# pub.net
KiCad netlist of a schematic drawn in EAGLE
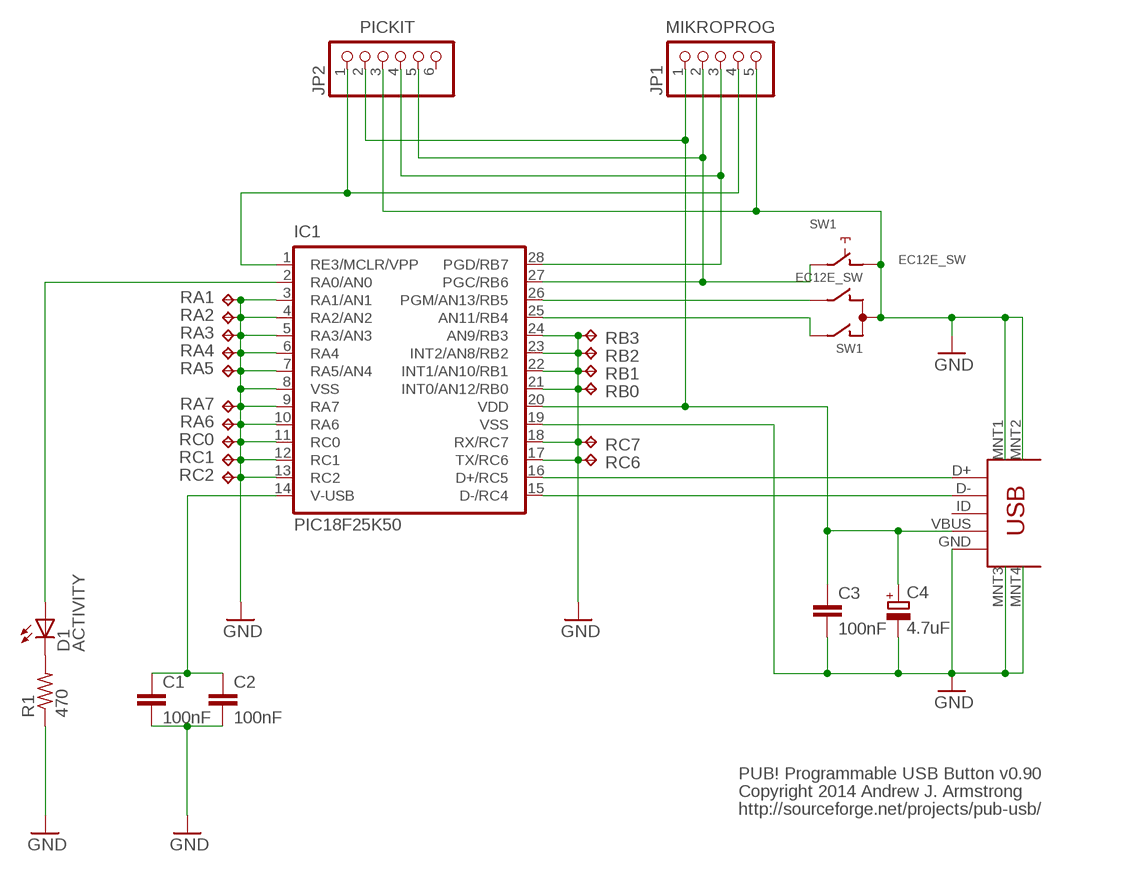
[diagram p0: schematic, sheet 1]

(export (version "E")
  (design (tool "Eeschema 10.0.6"))
  (components
    (comp (ref "C1")
      (value "100nF")
      (footprint "eagle-import:C0805")
      (libsource (lib "eagle-import") (part "C-EUC0805"))
    )
    (comp (ref "C2")
      (value "100nF")
      (footprint "eagle-import:C0805")
      (libsource (lib "eagle-import") (part "C-EUC0805"))
    )
    (comp (ref "C3")
      (value "100nF")
      (footprint "eagle-import:C0805")
      (libsource (lib "eagle-import") (part "C-EUC0805"))
    )
    (comp (ref "C4")
      (value "4.7uF")
      (footprint "eagle-import:SMC_A")
      (libsource (lib "eagle-import") (part "CPOL-EUSMCA"))
    )
    (comp (ref "D1")
      (value "ACTIVITY")
      (footprint "eagle-import:SML1206")
      (libsource (lib "eagle-import") (part "LEDSML1206"))
    )
    (comp (ref "IC1")
      (value "PIC18F25K50")
      (footprint "eagle-import:SO28W")
      (libsource (lib "eagle-import") (part "PIC18F25K50SO28W"))
    )
    (comp (ref "JP1")
      (value "MIKROPROG")
      (footprint "eagle-import:1X05_90")
      (libsource (lib "eagle-import") (part "PINHD-1X5/90"))
    )
    (comp (ref "JP2")
      (value "PICKIT")
      (footprint "eagle-import:1X06_90")
      (libsource (lib "eagle-import") (part "PINHD-1X6/90"))
    )
    (comp (ref "JP3")
      (value "USB-MINIB-5PIN")
      (footprint "eagle-import:USB-MINIB")
      (libsource (lib "eagle-import") (part "USB-MINIB-5PIN"))
    )
    (comp (ref "R1")
      (value "470")
      (footprint "eagle-import:M1206")
      (libsource (lib "eagle-import") (part "R-US_M1206"))
    )
    (comp (ref "RA1")
      (value "TPB1,27")
      (footprint "eagle-import:B1,27")
      (libsource (lib "eagle-import") (part "TPB1,27"))
    )
    (comp (ref "RA2")
      (value "TPB1,27")
      (footprint "eagle-import:B1,27")
      (libsource (lib "eagle-import") (part "TPB1,27"))
    )
    (comp (ref "RA3")
      (value "TPB1,27")
      (footprint "eagle-import:B1,27")
      (libsource (lib "eagle-import") (part "TPB1,27"))
    )
    (comp (ref "RA4")
      (value "TPB1,27")
      (footprint "eagle-import:B1,27")
      (libsource (lib "eagle-import") (part "TPB1,27"))
    )
    (comp (ref "RA5")
      (value "TPB1,27")
      (footprint "eagle-import:B1,27")
      (libsource (lib "eagle-import") (part "TPB1,27"))
    )
    (comp (ref "RA6")
      (value "TPB1,27")
      (footprint "eagle-import:B1,27")
      (libsource (lib "eagle-import") (part "TPB1,27"))
    )
    (comp (ref "RA7")
      (value "TPB1,27")
      (footprint "eagle-import:B1,27")
      (libsource (lib "eagle-import") (part "TPB1,27"))
    )
    (comp (ref "RB0")
      (value "TPB1,27")
      (footprint "eagle-import:B1,27")
      (libsource (lib "eagle-import") (part "TPB1,27"))
    )
    (comp (ref "RB1")
      (value "TPB1,27")
      (footprint "eagle-import:B1,27")
      (libsource (lib "eagle-import") (part "TPB1,27"))
    )
    (comp (ref "RB2")
      (value "TPB1,27")
      (footprint "eagle-import:B1,27")
      (libsource (lib "eagle-import") (part "TPB1,27"))
    )
    (comp (ref "RB3")
      (value "TPB1,27")
      (footprint "eagle-import:B1,27")
      (libsource (lib "eagle-import") (part "TPB1,27"))
    )
    (comp (ref "RC0")
      (value "TPB1,27")
      (footprint "eagle-import:B1,27")
      (libsource (lib "eagle-import") (part "TPB1,27"))
    )
    (comp (ref "RC1")
      (value "TPB1,27")
      (footprint "eagle-import:B1,27")
      (libsource (lib "eagle-import") (part "TPB1,27"))
    )
    (comp (ref "RC2")
      (value "TPB1,27")
      (footprint "eagle-import:B1,27")
      (libsource (lib "eagle-import") (part "TPB1,27"))
    )
    (comp (ref "RC6")
      (value "TPB1,27")
      (footprint "eagle-import:B1,27")
      (libsource (lib "eagle-import") (part "TPB1,27"))
    )
    (comp (ref "RC7")
      (value "TPB1,27")
      (footprint "eagle-import:B1,27")
      (libsource (lib "eagle-import") (part "TPB1,27"))
    )
    (comp (ref "SW1")
      (value "EC12E_SW")
      (footprint "eagle-import:ALPS_EC12E_SW")
      (fields (field (name "MPN") "EC12E2424407"))
      (libsource (lib "eagle-import") (part "EC12E_SW"))
    )
  )
  (nets
    (net (code "1") (name "GND") (class "Default")
      (node (ref "C1") (pin "2") (pinfunction "2_2") (pintype "passive"))
      (node (ref "C2") (pin "2") (pinfunction "2_2") (pintype "passive"))
      (node (ref "C3") (pin "2") (pinfunction "2_2") (pintype "passive"))
      (node (ref "C4") (pin "-") (pinfunction "-_-") (pintype "passive"))
      (node (ref "IC1") (pin "10") (pinfunction "RA6_10") (pintype "bidirectional"))
      (node (ref "IC1") (pin "11") (pinfunction "RC0_11") (pintype "bidirectional"))
      (node (ref "IC1") (pin "12") (pinfunction "RC1_12") (pintype "bidirectional"))
      (node (ref "IC1") (pin "13") (pinfunction "RC2_13") (pintype "bidirectional"))
      (node (ref "IC1") (pin "17") (pinfunction "TX/RC6_17") (pintype "bidirectional"))
      (node (ref "IC1") (pin "18") (pinfunction "RX/RC7_18") (pintype "bidirectional"))
      (node (ref "IC1") (pin "19") (pinfunction "VSS_19") (pintype "power_in"))
      (node (ref "IC1") (pin "21") (pinfunction "INT0/AN12/RB0_21") (pintype "bidirectional"))
      (node (ref "IC1") (pin "22") (pinfunction "INT1/AN10/RB1_22") (pintype "bidirectional"))
      (node (ref "IC1") (pin "23") (pinfunction "INT2/AN8/RB2_23") (pintype "bidirectional"))
      (node (ref "IC1") (pin "24") (pinfunction "AN9/RB3_24") (pintype "bidirectional"))
      (node (ref "IC1") (pin "3") (pinfunction "RA1/AN1_3") (pintype "bidirectional"))
      (node (ref "IC1") (pin "4") (pinfunction "RA2/AN2_4") (pintype "bidirectional"))
      (node (ref "IC1") (pin "5") (pinfunction "RA3/AN3_5") (pintype "bidirectional"))
      (node (ref "IC1") (pin "6") (pinfunction "RA4_6") (pintype "bidirectional"))
      (node (ref "IC1") (pin "7") (pinfunction "RA5/AN4_7") (pintype "bidirectional"))
      (node (ref "IC1") (pin "8") (pinfunction "VSS_8") (pintype "power_in"))
      (node (ref "IC1") (pin "9") (pinfunction "RA7_9") (pintype "bidirectional"))
      (node (ref "JP1") (pin "5") (pinfunction "5_5") (pintype "passive"))
      (node (ref "JP2") (pin "3") (pinfunction "3_3") (pintype "passive"))
      (node (ref "JP3") (pin "GND") (pinfunction "GND_GND") (pintype "bidirectional"))
      (node (ref "JP3") (pin "MNT1") (pinfunction "MNT1_MNT1") (pintype "bidirectional"))
      (node (ref "JP3") (pin "MNT2") (pinfunction "MNT2_MNT2") (pintype "bidirectional"))
      (node (ref "JP3") (pin "MNT3") (pinfunction "MNT3_MNT3") (pintype "bidirectional"))
      (node (ref "JP3") (pin "MNT4") (pinfunction "MNT4_MNT4") (pintype "bidirectional"))
      (node (ref "R1") (pin "1") (pinfunction "1_1") (pintype "passive"))
      (node (ref "RA1") (pin "TP") (pinfunction "TP_TP") (pintype "input"))
      (node (ref "RA2") (pin "TP") (pinfunction "TP_TP") (pintype "input"))
      (node (ref "RA3") (pin "TP") (pinfunction "TP_TP") (pintype "input"))
      (node (ref "RA4") (pin "TP") (pinfunction "TP_TP") (pintype "input"))
      (node (ref "RA5") (pin "TP") (pinfunction "TP_TP") (pintype "input"))
      (node (ref "RA6") (pin "TP") (pinfunction "TP_TP") (pintype "input"))
      (node (ref "RA7") (pin "TP") (pinfunction "TP_TP") (pintype "input"))
      (node (ref "RB0") (pin "TP") (pinfunction "TP_TP") (pintype "input"))
      (node (ref "RB1") (pin "TP") (pinfunction "TP_TP") (pintype "input"))
      (node (ref "RB2") (pin "TP") (pinfunction "TP_TP") (pintype "input"))
      (node (ref "RB3") (pin "TP") (pinfunction "TP_TP") (pintype "input"))
      (node (ref "RC0") (pin "TP") (pinfunction "TP_TP") (pintype "input"))
      (node (ref "RC1") (pin "TP") (pinfunction "TP_TP") (pintype "input"))
      (node (ref "RC2") (pin "TP") (pinfunction "TP_TP") (pintype "input"))
      (node (ref "RC6") (pin "TP") (pinfunction "TP_TP") (pintype "input"))
      (node (ref "RC7") (pin "TP") (pinfunction "TP_TP") (pintype "input"))
      (node (ref "SW1") (pin "C") (pinfunction "C_C") (pintype "passive"))
      (node (ref "SW1") (pin "D") (pinfunction "1_D") (pintype "passive"))
    )
    (net (code "2") (name "Net-(D1-PadC)") (class "Default")
      (node (ref "D1") (pin "C") (pinfunction "C_C") (pintype "passive"))
      (node (ref "R1") (pin "2") (pinfunction "2_2") (pintype "passive"))
    )
    (net (code "3") (name "Net-(IC1-AN11{slash}RB4)") (class "Default")
      (node (ref "IC1") (pin "25") (pinfunction "AN11/RB4_25") (pintype "bidirectional"))
      (node (ref "SW1") (pin "A") (pinfunction "A_A") (pintype "passive"))
    )
    (net (code "4") (name "Net-(IC1-D+{slash}RC5)") (class "Default")
      (node (ref "IC1") (pin "16") (pinfunction "D+/RC5_16") (pintype "bidirectional"))
      (node (ref "JP3") (pin "D+") (pinfunction "D+_D+") (pintype "bidirectional"))
    )
    (net (code "5") (name "Net-(IC1-D-{slash}RC4)") (class "Default")
      (node (ref "IC1") (pin "15") (pinfunction "D-/RC4_15") (pintype "bidirectional"))
      (node (ref "JP3") (pin "D-") (pinfunction "D-_D-") (pintype "bidirectional"))
    )
    (net (code "6") (name "Net-(IC1-PGC{slash}RB6)") (class "Default")
      (node (ref "IC1") (pin "27") (pinfunction "PGC/RB6_27") (pintype "bidirectional"))
      (node (ref "JP1") (pin "2") (pinfunction "2_2") (pintype "passive"))
      (node (ref "JP2") (pin "5") (pinfunction "5_5") (pintype "passive"))
      (node (ref "SW1") (pin "E") (pinfunction "2_E") (pintype "passive"))
    )
    (net (code "7") (name "Net-(IC1-PGD{slash}RB7)") (class "Default")
      (node (ref "IC1") (pin "28") (pinfunction "PGD/RB7_28") (pintype "bidirectional"))
      (node (ref "JP1") (pin "3") (pinfunction "3_3") (pintype "passive"))
      (node (ref "JP2") (pin "4") (pinfunction "4_4") (pintype "passive"))
    )
    (net (code "8") (name "Net-(IC1-PGM{slash}AN13{slash}RB5)") (class "Default")
      (node (ref "IC1") (pin "26") (pinfunction "PGM/AN13/RB5_26") (pintype "bidirectional"))
      (node (ref "SW1") (pin "B") (pinfunction "B_B") (pintype "passive"))
    )
    (net (code "9") (name "Net-(IC1-RA0{slash}AN0)") (class "Default")
      (node (ref "D1") (pin "A") (pinfunction "A_A") (pintype "passive"))
      (node (ref "IC1") (pin "2") (pinfunction "RA0/AN0_2") (pintype "bidirectional"))
    )
    (net (code "10") (name "Net-(IC1-RE3{slash}MCLR{slash}VPP)") (class "Default")
      (node (ref "IC1") (pin "1") (pinfunction "RE3/MCLR/VPP_1") (pintype "bidirectional"))
      (node (ref "JP1") (pin "4") (pinfunction "4_4") (pintype "passive"))
      (node (ref "JP2") (pin "1") (pinfunction "1_1") (pintype "passive"))
    )
    (net (code "11") (name "Net-(IC1-V-USB)") (class "Default")
      (node (ref "C1") (pin "1") (pinfunction "1_1") (pintype "passive"))
      (node (ref "C2") (pin "1") (pinfunction "1_1") (pintype "passive"))
      (node (ref "IC1") (pin "14") (pinfunction "V-USB_14") (pintype "bidirectional"))
    )
    (net (code "12") (name "Net-(IC1-VDD)") (class "Default")
      (node (ref "C3") (pin "1") (pinfunction "1_1") (pintype "passive"))
      (node (ref "C4") (pin "+") (pinfunction "+_+") (pintype "passive"))
      (node (ref "IC1") (pin "20") (pinfunction "VDD_20") (pintype "power_in"))
      (node (ref "JP1") (pin "1") (pinfunction "1_1") (pintype "passive"))
      (node (ref "JP2") (pin "2") (pinfunction "2_2") (pintype "passive"))
      (node (ref "JP3") (pin "VBUS") (pinfunction "VBUS_VBUS") (pintype "bidirectional"))
    )
    (net (code "13") (name "unconnected-(JP2-Pad6)") (class "Default")
      (node (ref "JP2") (pin "6") (pinfunction "6_6") (pintype "passive"))
    )
    (net (code "14") (name "unconnected-(JP3-PadID)") (class "Default")
      (node (ref "JP3") (pin "ID") (pinfunction "ID_ID") (pintype "bidirectional"))
    )
  )
)
